# led_shield.net
KiCad netlist of a schematic drawn in EAGLE
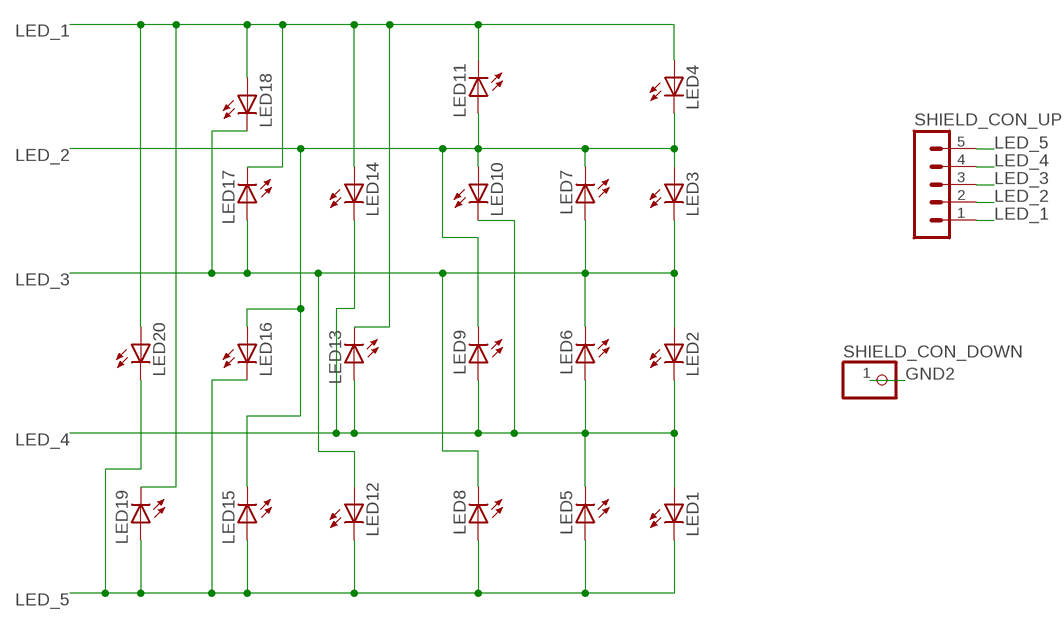
[diagram p0: schematic, sheet 1]

(export (version "E")
  (design (tool "Eeschema 10.0.6"))
  (components
    (comp (ref "LED1")
      (value "LEDCHIP-LED0603")
      (footprint "eagle-import:CHIP-LED0603")
      (libsource (lib "eagle-import") (part "LEDCHIP-LED0603"))
    )
    (comp (ref "LED2")
      (value "LEDCHIP-LED0603")
      (footprint "eagle-import:CHIP-LED0603")
      (libsource (lib "eagle-import") (part "LEDCHIP-LED0603"))
    )
    (comp (ref "LED3")
      (value "LEDCHIP-LED0603")
      (footprint "eagle-import:CHIP-LED0603")
      (libsource (lib "eagle-import") (part "LEDCHIP-LED0603"))
    )
    (comp (ref "LED4")
      (value "LEDCHIP-LED0603")
      (footprint "eagle-import:CHIP-LED0603")
      (libsource (lib "eagle-import") (part "LEDCHIP-LED0603"))
    )
    (comp (ref "LED5")
      (value "LEDCHIP-LED0603")
      (footprint "eagle-import:CHIP-LED0603")
      (libsource (lib "eagle-import") (part "LEDCHIP-LED0603"))
    )
    (comp (ref "LED6")
      (value "LEDCHIP-LED0603")
      (footprint "eagle-import:CHIP-LED0603")
      (libsource (lib "eagle-import") (part "LEDCHIP-LED0603"))
    )
    (comp (ref "LED7")
      (value "LEDCHIP-LED0603")
      (footprint "eagle-import:CHIP-LED0603")
      (libsource (lib "eagle-import") (part "LEDCHIP-LED0603"))
    )
    (comp (ref "LED8")
      (value "LEDCHIP-LED0603")
      (footprint "eagle-import:CHIP-LED0603")
      (libsource (lib "eagle-import") (part "LEDCHIP-LED0603"))
    )
    (comp (ref "LED9")
      (value "LEDCHIP-LED0603")
      (footprint "eagle-import:CHIP-LED0603")
      (libsource (lib "eagle-import") (part "LEDCHIP-LED0603"))
    )
    (comp (ref "LED10")
      (value "LEDCHIP-LED0603")
      (footprint "eagle-import:CHIP-LED0603")
      (libsource (lib "eagle-import") (part "LEDCHIP-LED0603"))
    )
    (comp (ref "LED11")
      (value "LEDCHIP-LED0603")
      (footprint "eagle-import:CHIP-LED0603")
      (libsource (lib "eagle-import") (part "LEDCHIP-LED0603"))
    )
    (comp (ref "LED12")
      (value "LEDCHIP-LED0603")
      (footprint "eagle-import:CHIP-LED0603")
      (libsource (lib "eagle-import") (part "LEDCHIP-LED0603"))
    )
    (comp (ref "LED13")
      (value "LEDCHIP-LED0603")
      (footprint "eagle-import:CHIP-LED0603")
      (libsource (lib "eagle-import") (part "LEDCHIP-LED0603"))
    )
    (comp (ref "LED14")
      (value "LEDCHIP-LED0603")
      (footprint "eagle-import:CHIP-LED0603")
      (libsource (lib "eagle-import") (part "LEDCHIP-LED0603"))
    )
    (comp (ref "LED15")
      (value "LEDCHIP-LED0603")
      (footprint "eagle-import:CHIP-LED0603")
      (libsource (lib "eagle-import") (part "LEDCHIP-LED0603"))
    )
    (comp (ref "LED16")
      (value "LEDCHIP-LED0603")
      (footprint "eagle-import:CHIP-LED0603")
      (libsource (lib "eagle-import") (part "LEDCHIP-LED0603"))
    )
    (comp (ref "LED17")
      (value "LEDCHIP-LED0603")
      (footprint "eagle-import:CHIP-LED0603")
      (libsource (lib "eagle-import") (part "LEDCHIP-LED0603"))
    )
    (comp (ref "LED18")
      (value "LEDCHIP-LED0603")
      (footprint "eagle-import:CHIP-LED0603")
      (libsource (lib "eagle-import") (part "LEDCHIP-LED0603"))
    )
    (comp (ref "LED19")
      (value "LEDCHIP-LED0603")
      (footprint "eagle-import:CHIP-LED0603")
      (libsource (lib "eagle-import") (part "LEDCHIP-LED0603"))
    )
    (comp (ref "LED20")
      (value "LEDCHIP-LED0603")
      (footprint "eagle-import:CHIP-LED0603")
      (libsource (lib "eagle-import") (part "LEDCHIP-LED0603"))
    )
    (comp (ref "SHIELD_CON_DOWN")
      (value "PINHD-1X1")
      (footprint "eagle-import:1X01")
      (libsource (lib "eagle-import") (part "PINHD-1X1"))
    )
    (comp (ref "SHIELD_CON_UP")
      (value "MA05-1")
      (footprint "eagle-import:MA05-1")
      (libsource (lib "eagle-import") (part "MA05-1"))
    )
  )
  (nets
    (net (code "1") (name "/GND2") (class "Default")
      (node (ref "SHIELD_CON_DOWN") (pin "1") (pinfunction "1_1") (pintype "passive"))
    )
    (net (code "2") (name "/LED_1") (class "Default")
      (node (ref "LED11") (pin "C") (pinfunction "C_C") (pintype "passive"))
      (node (ref "LED13") (pin "C") (pinfunction "C_C") (pintype "passive"))
      (node (ref "LED14") (pin "A") (pinfunction "A_A") (pintype "passive"))
      (node (ref "LED17") (pin "C") (pinfunction "C_C") (pintype "passive"))
      (node (ref "LED18") (pin "A") (pinfunction "A_A") (pintype "passive"))
      (node (ref "LED19") (pin "C") (pinfunction "C_C") (pintype "passive"))
      (node (ref "LED20") (pin "A") (pinfunction "A_A") (pintype "passive"))
      (node (ref "LED4") (pin "A") (pinfunction "A_A") (pintype "passive"))
      (node (ref "SHIELD_CON_UP") (pin "1") (pinfunction "1_1") (pintype "passive"))
    )
    (net (code "3") (name "/LED_2") (class "Default")
      (node (ref "LED10") (pin "A") (pinfunction "A_A") (pintype "passive"))
      (node (ref "LED11") (pin "A") (pinfunction "A_A") (pintype "passive"))
      (node (ref "LED15") (pin "C") (pinfunction "C_C") (pintype "passive"))
      (node (ref "LED16") (pin "A") (pinfunction "A_A") (pintype "passive"))
      (node (ref "LED3") (pin "A") (pinfunction "A_A") (pintype "passive"))
      (node (ref "LED4") (pin "C") (pinfunction "C_C") (pintype "passive"))
      (node (ref "LED7") (pin "C") (pinfunction "C_C") (pintype "passive"))
      (node (ref "LED9") (pin "C") (pinfunction "C_C") (pintype "passive"))
      (node (ref "SHIELD_CON_UP") (pin "2") (pinfunction "2_2") (pintype "passive"))
    )
    (net (code "4") (name "/LED_3") (class "Default")
      (node (ref "LED12") (pin "A") (pinfunction "A_A") (pintype "passive"))
      (node (ref "LED17") (pin "A") (pinfunction "A_A") (pintype "passive"))
      (node (ref "LED18") (pin "C") (pinfunction "C_C") (pintype "passive"))
      (node (ref "LED2") (pin "A") (pinfunction "A_A") (pintype "passive"))
      (node (ref "LED3") (pin "C") (pinfunction "C_C") (pintype "passive"))
      (node (ref "LED6") (pin "C") (pinfunction "C_C") (pintype "passive"))
      (node (ref "LED7") (pin "A") (pinfunction "A_A") (pintype "passive"))
      (node (ref "LED8") (pin "C") (pinfunction "C_C") (pintype "passive"))
      (node (ref "SHIELD_CON_UP") (pin "3") (pinfunction "3_3") (pintype "passive"))
    )
    (net (code "5") (name "/LED_4") (class "Default")
      (node (ref "LED1") (pin "A") (pinfunction "A_A") (pintype "passive"))
      (node (ref "LED10") (pin "C") (pinfunction "C_C") (pintype "passive"))
      (node (ref "LED13") (pin "A") (pinfunction "A_A") (pintype "passive"))
      (node (ref "LED14") (pin "C") (pinfunction "C_C") (pintype "passive"))
      (node (ref "LED2") (pin "C") (pinfunction "C_C") (pintype "passive"))
      (node (ref "LED5") (pin "C") (pinfunction "C_C") (pintype "passive"))
      (node (ref "LED6") (pin "A") (pinfunction "A_A") (pintype "passive"))
      (node (ref "LED9") (pin "A") (pinfunction "A_A") (pintype "passive"))
      (node (ref "SHIELD_CON_UP") (pin "4") (pinfunction "4_4") (pintype "passive"))
    )
    (net (code "6") (name "/LED_5") (class "Default")
      (node (ref "LED1") (pin "C") (pinfunction "C_C") (pintype "passive"))
      (node (ref "LED12") (pin "C") (pinfunction "C_C") (pintype "passive"))
      (node (ref "LED15") (pin "A") (pinfunction "A_A") (pintype "passive"))
      (node (ref "LED16") (pin "C") (pinfunction "C_C") (pintype "passive"))
      (node (ref "LED19") (pin "A") (pinfunction "A_A") (pintype "passive"))
      (node (ref "LED20") (pin "C") (pinfunction "C_C") (pintype "passive"))
      (node (ref "LED5") (pin "A") (pinfunction "A_A") (pintype "passive"))
      (node (ref "LED8") (pin "A") (pinfunction "A_A") (pintype "passive"))
      (node (ref "SHIELD_CON_UP") (pin "5") (pinfunction "5_5") (pintype "passive"))
    )
  )
)
